# SSRoof.net
KiCad netlist of a schematic drawn in Altium Designer
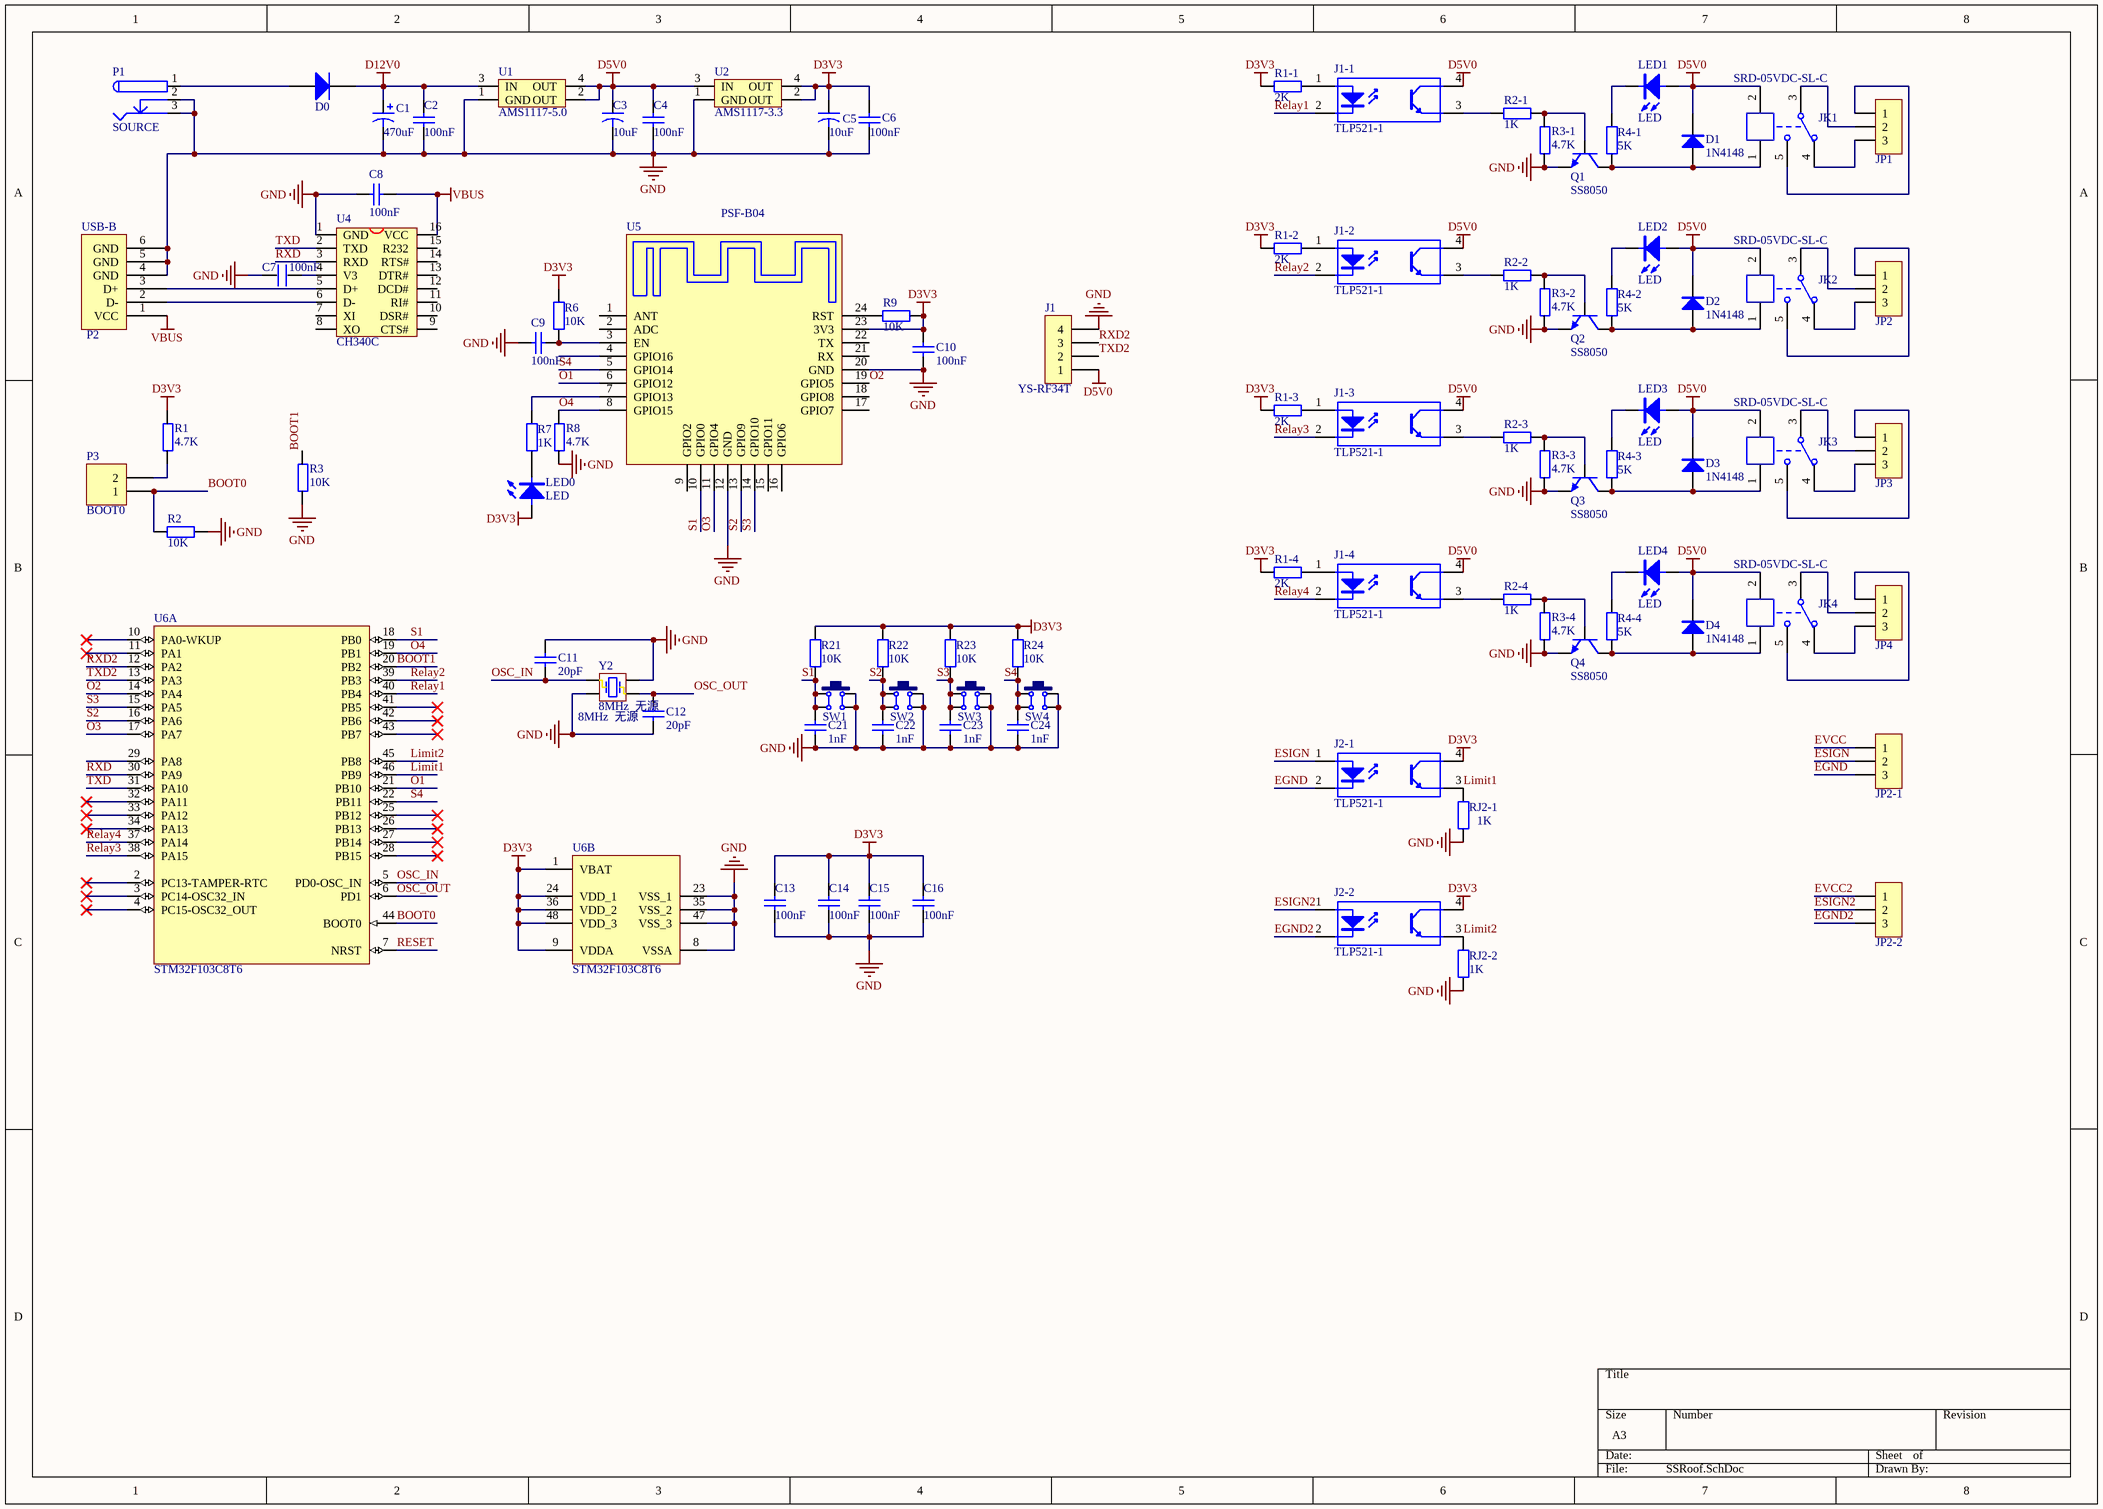
[diagram p0: SSRoof.SchDoc]

(export (version "E")
  (design (tool "Eeschema 10.0.6"))
  (components
    (comp (ref "C1")
      (value "470uF")
      (footprint "CAP8")
      (description "470UF      16V      CD10X10D5")
      (libsource (lib "平台原理图symbol图库V1.0") (part "C470UF016S"))
    )
    (comp (ref "C2")
      (value "100nF")
      (footprint "0603C")
      (description "Capacitor")
      (fields (field (name "PUBLISHER") "Altium Limited"))
      (libsource (lib "Crazy_PCB") (part "Cap"))
    )
    (comp (ref "C3")
      (value "10uF")
      (footprint "3216")
      (fields (field (name "VAULE") "10uF"))
      (libsource (lib "Crazy_PCB") (part "CAP2"))
    )
    (comp (ref "C4")
      (value "100nF")
      (footprint "0603C")
      (description "Capacitor")
      (fields (field (name "PUBLISHER") "Altium Limited"))
      (libsource (lib "Crazy_PCB") (part "Cap"))
    )
    (comp (ref "C5")
      (value "10uF")
      (footprint "3216")
      (fields (field (name "VAULE") "10uF"))
      (libsource (lib "Crazy_PCB") (part "CAP2"))
    )
    (comp (ref "C6")
      (value "100nF")
      (footprint "0603C")
      (description "Capacitor")
      (fields (field (name "PUBLISHER") "Altium Limited"))
      (libsource (lib "Crazy_PCB") (part "Cap"))
    )
    (comp (ref "C7")
      (value "100nF")
      (footprint "0603C")
      (libsource (lib "WarShip V3 STM32103封装库") (part "C"))
    )
    (comp (ref "C8")
      (value "100nF")
      (footprint "0603C")
      (description "Capacitor")
      (fields (field (name "PUBLISHER") "Altium Limited"))
      (libsource (lib "Crazy_PCB") (part "Cap"))
    )
    (comp (ref "C9")
      (value "100nF")
      (footprint "0603C")
      (description "Capacitor")
      (fields (field (name "PUBLISHER") "Altium Limited"))
      (libsource (lib "Crazy_PCB") (part "Cap"))
    )
    (comp (ref "C10")
      (value "100nF")
      (footprint "0603C")
      (description "Capacitor")
      (fields (field (name "PUBLISHER") "Altium Limited"))
      (libsource (lib "Crazy_PCB") (part "Cap"))
    )
    (comp (ref "C11")
      (value "20pF")
      (footprint "0603C")
      (description "Capacitor")
      (fields (field (name "PUBLISHER") "Altium Limited"))
      (libsource (lib "JL_SCH") (part "Cap"))
    )
    (comp (ref "C12")
      (value "20pF")
      (footprint "0603C")
      (description "Capacitor")
      (fields (field (name "PUBLISHER") "Altium Limited"))
      (libsource (lib "JL_SCH") (part "Cap"))
    )
    (comp (ref "C13")
      (value "100nF")
      (footprint "0603C")
      (description "Capacitor")
      (fields (field (name "PUBLISHER") "Altium Limited"))
      (libsource (lib "Crazy_PCB") (part "Cap"))
    )
    (comp (ref "C14")
      (value "100nF")
      (footprint "0603C")
      (description "Capacitor")
      (fields (field (name "PUBLISHER") "Altium Limited"))
      (libsource (lib "Crazy_PCB") (part "Cap"))
    )
    (comp (ref "C15")
      (value "100nF")
      (footprint "0603C")
      (description "Capacitor")
      (fields (field (name "PUBLISHER") "Altium Limited"))
      (libsource (lib "Crazy_PCB") (part "Cap"))
    )
    (comp (ref "C16")
      (value "100nF")
      (footprint "0603C")
      (description "Capacitor")
      (fields (field (name "PUBLISHER") "Altium Limited"))
      (libsource (lib "Crazy_PCB") (part "Cap"))
    )
    (comp (ref "C21")
      (value "1nF")
      (footprint "0603C")
      (description "Capacitor")
      (fields (field (name "PUBLISHER") "Altium Limited"))
      (libsource (lib "JL_SCH") (part "Cap"))
    )
    (comp (ref "C22")
      (value "1nF")
      (footprint "0603C")
      (description "Capacitor")
      (fields (field (name "PUBLISHER") "Altium Limited"))
      (libsource (lib "JL_SCH") (part "Cap"))
    )
    (comp (ref "C23")
      (value "1nF")
      (footprint "0603C")
      (description "Capacitor")
      (fields (field (name "PUBLISHER") "Altium Limited"))
      (libsource (lib "JL_SCH") (part "Cap"))
    )
    (comp (ref "C24")
      (value "1nF")
      (footprint "0603C")
      (description "Capacitor")
      (fields (field (name "PUBLISHER") "Altium Limited"))
      (libsource (lib "JL_SCH") (part "Cap"))
    )
    (comp (ref "D0")
      (value "M7")
      (footprint "DO-214AC")
      (description "High Conductance Fast Diode")
      (fields (field (name "PUBLISHER") "Altium Limited"))
      (libsource (lib "Crazy_PCB") (part "Diode"))
    )
    (comp (ref "D1")
      (value "1N4148")
      (footprint "SOD-323")
      (description "高速开关二极管")
      (fields (field (name "版权归属") "源创客"))
      (libsource (lib "8.1   - 二极管-整流桥") (part "1N4148"))
    )
    (comp (ref "D2")
      (value "1N4148")
      (footprint "SOD-323")
      (description "高速开关二极管")
      (fields (field (name "版权归属") "源创客"))
      (libsource (lib "8.1   - 二极管-整流桥") (part "1N4148"))
    )
    (comp (ref "D3")
      (value "1N4148")
      (footprint "SOD-323")
      (description "高速开关二极管")
      (fields (field (name "版权归属") "源创客"))
      (libsource (lib "8.1   - 二极管-整流桥") (part "1N4148"))
    )
    (comp (ref "D4")
      (value "1N4148")
      (footprint "SOD-323")
      (description "高速开关二极管")
      (fields (field (name "版权归属") "源创客"))
      (libsource (lib "8.1   - 二极管-整流桥") (part "1N4148"))
    )
    (comp (ref "J1")
      (value "YS-RF34T")
      (footprint "PIN-4-2.54-1.0")
      (description "Connector")
      (libsource (lib "General") (part "HDR1x4"))
    )
    (comp (ref "J1-1")
      (value "TLP521-1")
      (footprint "SOP4-W2.54_M")
      (description "1路开关光耦")
      (fields (field (name "版权归属") "源创客"))
      (libsource (lib "11.1 - 传感元件") (part "TLP521-1"))
    )
    (comp (ref "J1-2")
      (value "TLP521-1")
      (footprint "SOP4-W2.54_M")
      (description "1路开关光耦")
      (fields (field (name "版权归属") "源创客"))
      (libsource (lib "11.1 - 传感元件") (part "TLP521-1"))
    )
    (comp (ref "J1-3")
      (value "TLP521-1")
      (footprint "SOP4-W2.54_M")
      (description "1路开关光耦")
      (fields (field (name "版权归属") "源创客"))
      (libsource (lib "11.1 - 传感元件") (part "TLP521-1"))
    )
    (comp (ref "J1-4")
      (value "TLP521-1")
      (footprint "SOP4-W2.54_M")
      (description "1路开关光耦")
      (fields (field (name "版权归属") "源创客"))
      (libsource (lib "11.1 - 传感元件") (part "TLP521-1"))
    )
    (comp (ref "J2-1")
      (value "TLP521-1")
      (footprint "SOP4-W2.54_M")
      (description "1路开关光耦")
      (fields (field (name "版权归属") "源创客"))
      (libsource (lib "11.1 - 传感元件") (part "TLP521-1"))
    )
    (comp (ref "J2-2")
      (value "TLP521-1")
      (footprint "SOP4-W2.54_M")
      (description "1路开关光耦")
      (fields (field (name "版权归属") "源创客"))
      (libsource (lib "11.1 - 传感元件") (part "TLP521-1"))
    )
    (comp (ref "JK1")
      (value "SRD-05VDC-SL-C")
      (footprint "SRD-C_B")
      (description "5V一组转换")
      (fields (field (name "版权归属") "源创客"))
      (libsource (lib "7.1   - 继电器") (part "SRD-05VDC-SL-C"))
    )
    (comp (ref "JK2")
      (value "SRD-05VDC-SL-C")
      (footprint "SRD-C_B")
      (description "5V一组转换")
      (fields (field (name "版权归属") "源创客"))
      (libsource (lib "7.1   - 继电器") (part "SRD-05VDC-SL-C"))
    )
    (comp (ref "JK3")
      (value "SRD-05VDC-SL-C")
      (footprint "SRD-C_B")
      (description "5V一组转换")
      (fields (field (name "版权归属") "源创客"))
      (libsource (lib "7.1   - 继电器") (part "SRD-05VDC-SL-C"))
    )
    (comp (ref "JK4")
      (value "SRD-05VDC-SL-C")
      (footprint "SRD-C_B")
      (description "5V一组转换")
      (fields (field (name "版权归属") "源创客"))
      (libsource (lib "7.1   - 继电器") (part "SRD-05VDC-SL-C"))
    )
    (comp (ref "JP1")
      (value "HDR-1X3")
      (footprint "KF2EDGK5.0-LI-3P")
      (description "3P接插件")
      (fields (field (name "版权归属") "源创客"))
      (libsource (lib "4.9   - 接插件-脚距5.0") (part "Header 3"))
    )
    (comp (ref "JP2")
      (value "HDR-1X3")
      (footprint "KF2EDGK5.0-LI-3P")
      (description "3P接插件")
      (fields (field (name "版权归属") "源创客"))
      (libsource (lib "4.9   - 接插件-脚距5.0") (part "Header 3"))
    )
    (comp (ref "JP2-1")
      (value "HDR-1X3")
      (footprint "KF2EDGK5.0-LI-3P")
      (description "3P接插件")
      (fields (field (name "版权归属") "源创客"))
      (libsource (lib "4.9   - 接插件-脚距5.0") (part "Header 3"))
    )
    (comp (ref "JP2-2")
      (value "HDR-1X3")
      (footprint "KF2EDGK5.0-LI-3P")
      (description "3P接插件")
      (fields (field (name "版权归属") "源创客"))
      (libsource (lib "4.9   - 接插件-脚距5.0") (part "Header 3"))
    )
    (comp (ref "JP3")
      (value "HDR-1X3")
      (footprint "KF2EDGK5.0-LI-3P")
      (description "3P接插件")
      (fields (field (name "版权归属") "源创客"))
      (libsource (lib "4.9   - 接插件-脚距5.0") (part "Header 3"))
    )
    (comp (ref "JP4")
      (value "HDR-1X3")
      (footprint "KF2EDGK5.0-LI-3P")
      (description "3P接插件")
      (fields (field (name "版权归属") "源创客"))
      (libsource (lib "4.9   - 接插件-脚距5.0") (part "Header 3"))
    )
    (comp (ref "LED0") (value "LED") (footprint "LED-0603") (libsource (lib "General") (part "LED")))
    (comp (ref "LED1") (value "LED") (footprint "LED-0603") (libsource (lib "General") (part "LED")))
    (comp (ref "LED2") (value "LED") (footprint "LED-0603") (libsource (lib "General") (part "LED")))
    (comp (ref "LED3") (value "LED") (footprint "LED-0603") (libsource (lib "General") (part "LED")))
    (comp (ref "LED4") (value "LED") (footprint "LED-0603") (libsource (lib "General") (part "LED")))
    (comp (ref "P1")
      (value "SOURCE")
      (footprint "DC_5.5MM")
      (fields (field (name "PUBLISHER") "Altium Limited"))
      (libsource (lib "Crazy_PCB") (part "SOURCE"))
    )
    (comp (ref "P2") (value "USB-B") (footprint "USB-B") (libsource (lib "DX") (part "USB-B")))
    (comp (ref "P3")
      (value "BOOT0")
      (footprint "HDR1X2")
      (description "Header, 2-Pin")
      (fields (field (name "PUBLISHER") "Altium Limited"))
      (libsource (lib "Miscellaneous Connectors") (part "MHDR1X2"))
    )
    (comp (ref "Q1")
      (value "SS8050")
      (footprint "SOT23-3N")
      (description "高频放大-NPN型")
      (fields (field (name "版权归属") "源创客"))
      (libsource (lib "6.2   - 三极管") (part "8050-SMD"))
    )
    (comp (ref "Q2")
      (value "SS8050")
      (footprint "SOT23-3N")
      (description "高频放大-NPN型")
      (fields (field (name "版权归属") "源创客"))
      (libsource (lib "6.2   - 三极管") (part "8050-SMD"))
    )
    (comp (ref "Q3")
      (value "SS8050")
      (footprint "SOT23-3N")
      (description "高频放大-NPN型")
      (fields (field (name "版权归属") "源创客"))
      (libsource (lib "6.2   - 三极管") (part "8050-SMD"))
    )
    (comp (ref "Q4")
      (value "SS8050")
      (footprint "SOT23-3N")
      (description "高频放大-NPN型")
      (fields (field (name "版权归属") "源创客"))
      (libsource (lib "6.2   - 三极管") (part "8050-SMD"))
    )
    (comp (ref "R1") (value "4.7K") (footprint "0603R") (libsource (lib "WarShip V3 STM32103封装库") (part "R")))
    (comp (ref "R1-1")
      (value "2K")
      (footprint "0603R")
      (description "Resistor")
      (fields (field (name "PUBLISHER") "Altium Limited"))
      (libsource (lib "") (part "RES_1"))
    )
    (comp (ref "R1-2")
      (value "2K")
      (footprint "0603R")
      (description "Resistor")
      (fields (field (name "PUBLISHER") "Altium Limited"))
      (libsource (lib "") (part "RES_1"))
    )
    (comp (ref "R1-3")
      (value "2K")
      (footprint "0603R")
      (description "Resistor")
      (fields (field (name "PUBLISHER") "Altium Limited"))
      (libsource (lib "") (part "RES_1"))
    )
    (comp (ref "R1-4")
      (value "2K")
      (footprint "0603R")
      (description "Resistor")
      (fields (field (name "PUBLISHER") "Altium Limited"))
      (libsource (lib "") (part "RES_1"))
    )
    (comp (ref "R2")
      (value "10K")
      (footprint "0603R")
      (description "Resistor")
      (fields (field (name "PUBLISHER") "Altium Limited"))
      (libsource (lib "Crazy_PCB") (part "RES"))
    )
    (comp (ref "R2-1")
      (value "1K")
      (footprint "0603R")
      (description "Resistor")
      (fields (field (name "PUBLISHER") "Altium Limited"))
      (libsource (lib "") (part "RES_1"))
    )
    (comp (ref "R2-2")
      (value "1K")
      (footprint "0603R")
      (description "Resistor")
      (fields (field (name "PUBLISHER") "Altium Limited"))
      (libsource (lib "") (part "RES_1"))
    )
    (comp (ref "R2-3")
      (value "1K")
      (footprint "0603R")
      (description "Resistor")
      (fields (field (name "PUBLISHER") "Altium Limited"))
      (libsource (lib "") (part "RES_1"))
    )
    (comp (ref "R2-4")
      (value "1K")
      (footprint "0603R")
      (description "Resistor")
      (fields (field (name "PUBLISHER") "Altium Limited"))
      (libsource (lib "") (part "RES_1"))
    )
    (comp (ref "R3") (value "10K") (footprint "0603R") (libsource (lib "WarShip V3 STM32103封装库") (part "R")))
    (comp (ref "R3-1")
      (value "4.7K")
      (footprint "0603R")
      (libsource (lib "WarShip V3 STM32103封装库") (part "R"))
    )
    (comp (ref "R3-2")
      (value "4.7K")
      (footprint "0603R")
      (libsource (lib "WarShip V3 STM32103封装库") (part "R"))
    )
    (comp (ref "R3-3")
      (value "4.7K")
      (footprint "0603R")
      (libsource (lib "WarShip V3 STM32103封装库") (part "R"))
    )
    (comp (ref "R3-4")
      (value "4.7K")
      (footprint "0603R")
      (libsource (lib "WarShip V3 STM32103封装库") (part "R"))
    )
    (comp (ref "R4-1")
      (value "5K")
      (footprint "0603R")
      (description "Resistor")
      (fields (field (name "PUBLISHER") "Altium Limited"))
      (libsource (lib "") (part "RES_3"))
    )
    (comp (ref "R4-2")
      (value "5K")
      (footprint "0603R")
      (description "Resistor")
      (fields (field (name "PUBLISHER") "Altium Limited"))
      (libsource (lib "") (part "RES_3"))
    )
    (comp (ref "R4-3")
      (value "5K")
      (footprint "0603R")
      (description "Resistor")
      (fields (field (name "PUBLISHER") "Altium Limited"))
      (libsource (lib "") (part "RES_3"))
    )
    (comp (ref "R4-4")
      (value "5K")
      (footprint "0603R")
      (description "Resistor")
      (fields (field (name "PUBLISHER") "Altium Limited"))
      (libsource (lib "") (part "RES_3"))
    )
    (comp (ref "R6")
      (value "10K")
      (footprint "0603R")
      (description "Resistor")
      (fields (field (name "PUBLISHER") "Altium Limited"))
      (libsource (lib "") (part "RES_2"))
    )
    (comp (ref "R7")
      (value "1K")
      (footprint "0603R")
      (description "Resistor")
      (fields (field (name "PUBLISHER") "Altium Limited"))
      (libsource (lib "") (part "RES_3"))
    )
    (comp (ref "R8") (value "4.7K") (footprint "0603R") (libsource (lib "WarShip V3 STM32103封装库") (part "R")))
    (comp (ref "R9")
      (value "10K")
      (footprint "0603R")
      (description "Resistor")
      (fields (field (name "PUBLISHER") "Altium Limited"))
      (libsource (lib "Crazy_PCB") (part "RES"))
    )
    (comp (ref "R21")
      (value "10K")
      (footprint "0603R")
      (description "Resistor")
      (fields (field (name "PUBLISHER") "Altium Limited"))
      (libsource (lib "") (part "RES_2"))
    )
    (comp (ref "R22")
      (value "10K")
      (footprint "0603R")
      (description "Resistor")
      (fields (field (name "PUBLISHER") "Altium Limited"))
      (libsource (lib "") (part "RES_2"))
    )
    (comp (ref "R23")
      (value "10K")
      (footprint "0603R")
      (description "Resistor")
      (fields (field (name "PUBLISHER") "Altium Limited"))
      (libsource (lib "") (part "RES_2"))
    )
    (comp (ref "R24")
      (value "10K")
      (footprint "0603R")
      (description "Resistor")
      (fields (field (name "PUBLISHER") "Altium Limited"))
      (libsource (lib "") (part "RES_2"))
    )
    (comp (ref "RJ2-1")
      (value "1K")
      (footprint "0603R")
      (description "Resistor")
      (fields (field (name "PUBLISHER") "Altium Limited"))
      (libsource (lib "") (part "RES_2"))
    )
    (comp (ref "RJ2-2")
      (value "1K")
      (footprint "0603R")
      (description "Resistor")
      (fields (field (name "PUBLISHER") "Altium Limited"))
      (libsource (lib "") (part "RES_2"))
    )
    (comp (ref "SW1")
      (value "6x6x5")
      (footprint "TSW SMD-6*6*6")
      (description "贴片6x6轻触开关")
      (fields (field (name "版权归属") "源创客"))
      (libsource (lib "5.1   - 按键-开关") (part "TSW SMD-6x6"))
    )
    (comp (ref "SW2")
      (value "6x6x5")
      (footprint "TSW SMD-6*6*6")
      (description "贴片6x6轻触开关")
      (fields (field (name "版权归属") "源创客"))
      (libsource (lib "5.1   - 按键-开关") (part "TSW SMD-6x6"))
    )
    (comp (ref "SW3")
      (value "6x6x5")
      (footprint "TSW SMD-6*6*6")
      (description "贴片6x6轻触开关")
      (fields (field (name "版权归属") "源创客"))
      (libsource (lib "5.1   - 按键-开关") (part "TSW SMD-6x6"))
    )
    (comp (ref "SW4")
      (value "6x6x5")
      (footprint "TSW SMD-6*6*6")
      (description "贴片6x6轻触开关")
      (fields (field (name "版权归属") "源创客"))
      (libsource (lib "5.1   - 按键-开关") (part "TSW SMD-6x6"))
    )
    (comp (ref "U1")
      (value "AMS1117-5.0")
      (footprint "SOT223")
      (libsource (lib "MiniSTM32 V3.0封装库") (part "AMS1117"))
    )
    (comp (ref "U2")
      (value "AMS1117-3.3")
      (footprint "SOT223")
      (libsource (lib "MiniSTM32 V3.0封装库") (part "AMS1117"))
    )
    (comp (ref "U4")
      (value "CH340C")
      (footprint "SO-16")
      (description "USB2UART")
      (libsource (lib "WarShip V3 STM32103封装库") (part "CH340G"))
    )
    (comp (ref "U5") (value "PSF-B04") (footprint "PSF-B04") (libsource (lib "SS") (part "PSF-B04")))
    (comp (ref "U6")
      (value "STM32F103C8T6")
      (footprint "LQFP48_N")
      (libsource (lib "STMicroelectronics STM32 F1") (part "STM32F103C8T6"))
    )
    (comp (ref "Y2")
      (value "8MHz  无源")
      (footprint "X3225")
      (description "Crystal Oscillator")
      (fields (field (name "ALTIUM_VALUE") "8MHz  无源") (field (name "PUBLISHER") "Altium Limited"))
      (libsource (lib "JL_SCH") (part "XTAL_1"))
    )
  )
  (nets
    (net (code "1") (name "/BOOT0") (class "Default")
      (node (ref "P3") (pin "1") (pinfunction "1_1") (pintype "passive"))
      (node (ref "R2") (pin "1") (pinfunction "1_1") (pintype "passive"))
      (node (ref "U6") (pin "44") (pinfunction "BOOT0_44") (pintype "input"))
    )
    (net (code "2") (name "/BOOT1") (class "Default")
      (node (ref "R3") (pin "2") (pintype "passive"))
      (node (ref "U6") (pin "20") (pinfunction "PB2_20") (pintype "bidirectional"))
    )
    (net (code "3") (name "/EGND") (class "Default")
      (node (ref "J2-1") (pin "2") (pinfunction "K_2") (pintype "passive"))
      (node (ref "JP2-1") (pin "3") (pinfunction "3_3") (pintype "passive"))
    )
    (net (code "4") (name "/EGND2") (class "Default")
      (node (ref "J2-2") (pin "2") (pinfunction "K_2") (pintype "passive"))
      (node (ref "JP2-2") (pin "3") (pinfunction "3_3") (pintype "passive"))
    )
    (net (code "5") (name "/ESIGN") (class "Default")
      (node (ref "J2-1") (pin "1") (pinfunction "A_1") (pintype "passive"))
      (node (ref "JP2-1") (pin "2") (pinfunction "2_2") (pintype "passive"))
    )
    (net (code "6") (name "/ESIGN2") (class "Default")
      (node (ref "J2-2") (pin "1") (pinfunction "A_1") (pintype "passive"))
      (node (ref "JP2-2") (pin "2") (pinfunction "2_2") (pintype "passive"))
    )
    (net (code "7") (name "/EVCC") (class "Default")
      (node (ref "JP2-1") (pin "1") (pinfunction "1_1") (pintype "passive"))
    )
    (net (code "8") (name "/EVCC2") (class "Default")
      (node (ref "JP2-2") (pin "1") (pinfunction "1_1") (pintype "passive"))
    )
    (net (code "9") (name "/Limit1") (class "Default")
      (node (ref "J2-1") (pin "3") (pinfunction "E_3") (pintype "passive"))
      (node (ref "RJ2-1") (pin "2") (pinfunction "2_2") (pintype "passive"))
      (node (ref "U6") (pin "46") (pinfunction "PB9_46") (pintype "bidirectional"))
    )
    (net (code "10") (name "/Limit2") (class "Default")
      (node (ref "J2-2") (pin "3") (pinfunction "E_3") (pintype "passive"))
      (node (ref "RJ2-2") (pin "2") (pinfunction "2_2") (pintype "passive"))
      (node (ref "U6") (pin "45") (pinfunction "PB8_45") (pintype "bidirectional"))
    )
    (net (code "11") (name "/O1") (class "Default")
      (node (ref "U5") (pin "6") (pinfunction "GPIO12_6") (pintype "passive"))
      (node (ref "U6") (pin "21") (pinfunction "PB10_21") (pintype "bidirectional"))
    )
    (net (code "12") (name "/O2") (class "Default")
      (node (ref "U5") (pin "19") (pinfunction "GPIO5_19") (pintype "passive"))
      (node (ref "U6") (pin "14") (pinfunction "PA4_14") (pintype "bidirectional"))
    )
    (net (code "13") (name "/O3") (class "Default")
      (node (ref "U5") (pin "11") (pinfunction "GPIO4_11") (pintype "passive"))
      (node (ref "U6") (pin "17") (pinfunction "PA7_17") (pintype "bidirectional"))
    )
    (net (code "14") (name "/O4") (class "Default")
      (node (ref "R8") (pin "2") (pintype "passive"))
      (node (ref "U5") (pin "8") (pinfunction "GPIO15_8") (pintype "passive"))
      (node (ref "U6") (pin "19") (pinfunction "PB1_19") (pintype "bidirectional"))
    )
    (net (code "15") (name "/OSC_IN") (class "Default")
      (node (ref "C11") (pin "1") (pinfunction "1_1") (pintype "passive"))
      (node (ref "U6") (pin "5") (pinfunction "PD0-OSC_IN_5") (pintype "bidirectional"))
      (node (ref "Y2") (pin "1") (pinfunction "OSC1_1") (pintype "passive"))
    )
    (net (code "16") (name "/OSC_OUT") (class "Default")
      (node (ref "C12") (pin "1") (pinfunction "1_1") (pintype "passive"))
      (node (ref "U6") (pin "6") (pinfunction "PD1_6") (pintype "bidirectional"))
      (node (ref "Y2") (pin "3") (pinfunction "OSC2_3") (pintype "passive"))
    )
    (net (code "17") (name "/RESET") (class "Default")
      (node (ref "U6") (pin "7") (pinfunction "NRST_7") (pintype "bidirectional"))
    )
    (net (code "18") (name "/RXD") (class "Default")
      (node (ref "U4") (pin "3") (pinfunction "RXD_3") (pintype "passive"))
      (node (ref "U6") (pin "30") (pinfunction "PA9_30") (pintype "bidirectional"))
    )
    (net (code "19") (name "/RXD2") (class "Default")
      (node (ref "J1") (pin "3") (pinfunction "3_3") (pintype "passive"))
      (node (ref "U6") (pin "12") (pinfunction "PA2_12") (pintype "bidirectional"))
    )
    (net (code "20") (name "/Relay1") (class "Default")
      (node (ref "J1-1") (pin "2") (pinfunction "K_2") (pintype "passive"))
      (node (ref "U6") (pin "40") (pinfunction "PB4_40") (pintype "bidirectional"))
    )
    (net (code "21") (name "/Relay2") (class "Default")
      (node (ref "J1-2") (pin "2") (pinfunction "K_2") (pintype "passive"))
      (node (ref "U6") (pin "39") (pinfunction "PB3_39") (pintype "bidirectional"))
    )
    (net (code "22") (name "/Relay3") (class "Default")
      (node (ref "J1-3") (pin "2") (pinfunction "K_2") (pintype "passive"))
      (node (ref "U6") (pin "38") (pinfunction "PA15_38") (pintype "bidirectional"))
    )
    (net (code "23") (name "/Relay4") (class "Default")
      (node (ref "J1-4") (pin "2") (pinfunction "K_2") (pintype "passive"))
      (node (ref "U6") (pin "37") (pinfunction "PA14_37") (pintype "bidirectional"))
    )
    (net (code "24") (name "/S1") (class "Default")
      (node (ref "C21") (pin "1") (pinfunction "1_1") (pintype "passive"))
      (node (ref "R21") (pin "1") (pinfunction "1_1") (pintype "passive"))
      (node (ref "SW1") (pin "1") (pinfunction "1_1") (pintype "passive"))
      (node (ref "SW1") (pin "4") (pinfunction "4_4") (pintype "passive"))
      (node (ref "U5") (pin "10") (pinfunction "GPIO0_10") (pintype "passive"))
      (node (ref "U6") (pin "18") (pinfunction "PB0_18") (pintype "bidirectional"))
    )
    (net (code "25") (name "/S2") (class "Default")
      (node (ref "C22") (pin "1") (pinfunction "1_1") (pintype "passive"))
      (node (ref "R22") (pin "1") (pinfunction "1_1") (pintype "passive"))
      (node (ref "SW2") (pin "1") (pinfunction "1_1") (pintype "passive"))
      (node (ref "SW2") (pin "4") (pinfunction "4_4") (pintype "passive"))
      (node (ref "U5") (pin "13") (pinfunction "GPIO9_13") (pintype "passive"))
      (node (ref "U6") (pin "16") (pinfunction "PA6_16") (pintype "bidirectional"))
    )
    (net (code "26") (name "/S3") (class "Default")
      (node (ref "C23") (pin "1") (pinfunction "1_1") (pintype "passive"))
      (node (ref "R23") (pin "1") (pinfunction "1_1") (pintype "passive"))
      (node (ref "SW3") (pin "1") (pinfunction "1_1") (pintype "passive"))
      (node (ref "SW3") (pin "4") (pinfunction "4_4") (pintype "passive"))
      (node (ref "U5") (pin "14") (pinfunction "GPIO10_14") (pintype "passive"))
      (node (ref "U6") (pin "15") (pinfunction "PA5_15") (pintype "bidirectional"))
    )
    (net (code "27") (name "/S4") (class "Default")
      (node (ref "C24") (pin "1") (pinfunction "1_1") (pintype "passive"))
      (node (ref "R24") (pin "1") (pinfunction "1_1") (pintype "passive"))
      (node (ref "SW4") (pin "1") (pinfunction "1_1") (pintype "passive"))
      (node (ref "SW4") (pin "4") (pinfunction "4_4") (pintype "passive"))
      (node (ref "U5") (pin "5") (pinfunction "GPIO14_5") (pintype "passive"))
      (node (ref "U6") (pin "22") (pinfunction "PB11_22") (pintype "bidirectional"))
    )
    (net (code "28") (name "/TXD") (class "Default")
      (node (ref "U4") (pin "2") (pinfunction "TXD_2") (pintype "passive"))
      (node (ref "U6") (pin "31") (pinfunction "PA10_31") (pintype "bidirectional"))
    )
    (net (code "29") (name "/TXD2") (class "Default")
      (node (ref "J1") (pin "2") (pinfunction "2_2") (pintype "passive"))
      (node (ref "U6") (pin "13") (pinfunction "PA3_13") (pintype "bidirectional"))
    )
    (net (code "30") (name "D3V3") (class "Default")
      (node (ref "C10") (pin "1") (pinfunction "1_1") (pintype "passive"))
      (node (ref "C13") (pin "2") (pinfunction "2_2") (pintype "passive"))
      (node (ref "C14") (pin "2") (pinfunction "2_2") (pintype "passive"))
      (node (ref "C15") (pin "2") (pinfunction "2_2") (pintype "passive"))
      (node (ref "C16") (pin "2") (pinfunction "2_2") (pintype "passive"))
      (node (ref "C5") (pin "1") (pinfunction "1_1") (pintype "passive"))
      (node (ref "C6") (pin "2") (pinfunction "2_2") (pintype "passive"))
      (node (ref "J2-1") (pin "4") (pinfunction "C_4") (pintype "passive"))
      (node (ref "J2-2") (pin "4") (pinfunction "C_4") (pintype "passive"))
      (node (ref "LED0") (pin "1") (pinfunction "A_1") (pintype "passive"))
      (node (ref "R1") (pin "2") (pintype "passive"))
      (node (ref "R1-1") (pin "2") (pinfunction "2_2") (pintype "passive"))
      (node (ref "R1-2") (pin "2") (pinfunction "2_2") (pintype "passive"))
      (node (ref "R1-3") (pin "2") (pinfunction "2_2") (pintype "passive"))
      (node (ref "R1-4") (pin "2") (pinfunction "2_2") (pintype "passive"))
      (node (ref "R21") (pin "2") (pinfunction "2_2") (pintype "passive"))
      (node (ref "R22") (pin "2") (pinfunction "2_2") (pintype "passive"))
      (node (ref "R23") (pin "2") (pinfunction "2_2") (pintype "passive"))
      (node (ref "R24") (pin "2") (pinfunction "2_2") (pintype "passive"))
      (node (ref "R6") (pin "2") (pinfunction "2_2") (pintype "passive"))
      (node (ref "R9") (pin "2") (pinfunction "2_2") (pintype "passive"))
      (node (ref "U2") (pin "2") (pinfunction "OUT_2") (pintype "passive"))
      (node (ref "U2") (pin "4") (pinfunction "OUT_4") (pintype "passive"))
      (node (ref "U5") (pin "23") (pinfunction "3V3_23") (pintype "passive"))
      (node (ref "U6") (pin "1") (pinfunction "VBAT_1") (pintype "power_in"))
      (node (ref "U6") (pin "24") (pinfunction "VDD_1_24") (pintype "power_in"))
      (node (ref "U6") (pin "36") (pinfunction "VDD_2_36") (pintype "power_in"))
      (node (ref "U6") (pin "48") (pinfunction "VDD_3_48") (pintype "power_in"))
      (node (ref "U6") (pin "9") (pinfunction "VDDA_9") (pintype "power_in"))
    )
    (net (code "31") (name "D5V0") (class "Default")
      (node (ref "C3") (pin "1") (pinfunction "1_1") (pintype "passive"))
      (node (ref "C4") (pin "2") (pinfunction "2_2") (pintype "passive"))
      (node (ref "D1") (pin "2") (pinfunction "K_2") (pintype "passive"))
      (node (ref "D2") (pin "2") (pinfunction "K_2") (pintype "passive"))
      (node (ref "D3") (pin "2") (pinfunction "K_2") (pintype "passive"))
      (node (ref "D4") (pin "2") (pinfunction "K_2") (pintype "passive"))
      (node (ref "J1") (pin "1") (pinfunction "1_1") (pintype "passive"))
      (node (ref "J1-1") (pin "4") (pinfunction "C_4") (pintype "passive"))
      (node (ref "J1-2") (pin "4") (pinfunction "C_4") (pintype "passive"))
      (node (ref "J1-3") (pin "4") (pinfunction "C_4") (pintype "passive"))
      (node (ref "J1-4") (pin "4") (pinfunction "C_4") (pintype "passive"))
      (node (ref "JK1") (pin "2") (pinfunction "2_2") (pintype "passive"))
      (node (ref "JK2") (pin "2") (pinfunction "2_2") (pintype "passive"))
      (node (ref "JK3") (pin "2") (pinfunction "2_2") (pintype "passive"))
      (node (ref "JK4") (pin "2") (pinfunction "2_2") (pintype "passive"))
      (node (ref "LED1") (pin "1") (pinfunction "A_1") (pintype "passive"))
      (node (ref "LED2") (pin "1") (pinfunction "A_1") (pintype "passive"))
      (node (ref "LED3") (pin "1") (pinfunction "A_1") (pintype "passive"))
      (node (ref "LED4") (pin "1") (pinfunction "A_1") (pintype "passive"))
      (node (ref "U1") (pin "2") (pinfunction "OUT_2") (pintype "passive"))
      (node (ref "U1") (pin "4") (pinfunction "OUT_4") (pintype "passive"))
      (node (ref "U2") (pin "3") (pinfunction "IN_3") (pintype "passive"))
    )
    (net (code "32") (name "D12V0") (class "Default")
      (node (ref "C1") (pin "1") (pinfunction "1_1") (pintype "passive"))
      (node (ref "C2") (pin "2") (pinfunction "2_2") (pintype "passive"))
      (node (ref "D0") (pin "2") (pinfunction "K_2") (pintype "passive"))
      (node (ref "U1") (pin "3") (pinfunction "IN_3") (pintype "passive"))
    )
    (net (code "33") (name "GND") (class "Default")
      (node (ref "C1") (pin "2") (pinfunction "2_2") (pintype "passive"))
      (node (ref "C10") (pin "2") (pinfunction "2_2") (pintype "passive"))
      (node (ref "C11") (pin "2") (pinfunction "2_2") (pintype "passive"))
      (node (ref "C12") (pin "2") (pinfunction "2_2") (pintype "passive"))
      (node (ref "C13") (pin "1") (pinfunction "1_1") (pintype "passive"))
      (node (ref "C14") (pin "1") (pinfunction "1_1") (pintype "passive"))
      (node (ref "C15") (pin "1") (pinfunction "1_1") (pintype "passive"))
      (node (ref "C16") (pin "1") (pinfunction "1_1") (pintype "passive"))
      (node (ref "C2") (pin "1") (pinfunction "1_1") (pintype "passive"))
      (node (ref "C21") (pin "2") (pinfunction "2_2") (pintype "passive"))
      (node (ref "C22") (pin "2") (pinfunction "2_2") (pintype "passive"))
      (node (ref "C23") (pin "2") (pinfunction "2_2") (pintype "passive"))
      (node (ref "C24") (pin "2") (pinfunction "2_2") (pintype "passive"))
      (node (ref "C3") (pin "2") (pinfunction "2_2") (pintype "passive"))
      (node (ref "C4") (pin "1") (pinfunction "1_1") (pintype "passive"))
      (node (ref "C5") (pin "2") (pinfunction "2_2") (pintype "passive"))
      (node (ref "C6") (pin "1") (pinfunction "1_1") (pintype "passive"))
      (node (ref "C7") (pin "1") (pintype "passive"))
      (node (ref "C8") (pin "1") (pinfunction "1_1") (pintype "passive"))
      (node (ref "C9") (pin "2") (pinfunction "2_2") (pintype "passive"))
      (node (ref "J1") (pin "4") (pinfunction "4_4") (pintype "passive"))
      (node (ref "P1") (pin "2") (pinfunction "2_2") (pintype "power_in"))
      (node (ref "P1") (pin "3") (pinfunction "3_3") (pintype "power_in"))
      (node (ref "P2") (pin "4") (pinfunction "GND_4") (pintype "passive"))
      (node (ref "P2") (pin "5") (pinfunction "GND_5") (pintype "passive"))
      (node (ref "P2") (pin "6") (pinfunction "GND_6") (pintype "passive"))
      (node (ref "Q1") (pin "2") (pinfunction "E_2") (pintype "passive"))
      (node (ref "Q2") (pin "2") (pinfunction "E_2") (pintype "passive"))
      (node (ref "Q3") (pin "2") (pinfunction "E_2") (pintype "passive"))
      (node (ref "Q4") (pin "2") (pinfunction "E_2") (pintype "passive"))
      (node (ref "R2") (pin "2") (pinfunction "2_2") (pintype "passive"))
      (node (ref "R3") (pin "1") (pintype "passive"))
      (node (ref "R3-1") (pin "1") (pintype "passive"))
      (node (ref "R3-2") (pin "1") (pintype "passive"))
      (node (ref "R3-3") (pin "1") (pintype "passive"))
      (node (ref "R3-4") (pin "1") (pintype "passive"))
      (node (ref "R8") (pin "1") (pintype "passive"))
      (node (ref "RJ2-1") (pin "1") (pinfunction "1_1") (pintype "passive"))
      (node (ref "RJ2-2") (pin "1") (pinfunction "1_1") (pintype "passive"))
      (node (ref "SW1") (pin "2") (pinfunction "2_2") (pintype "passive"))
      (node (ref "SW1") (pin "3") (pinfunction "3_3") (pintype "passive"))
      (node (ref "SW2") (pin "2") (pinfunction "2_2") (pintype "passive"))
      (node (ref "SW2") (pin "3") (pinfunction "3_3") (pintype "passive"))
      (node (ref "SW3") (pin "2") (pinfunction "2_2") (pintype "passive"))
      (node (ref "SW3") (pin "3") (pinfunction "3_3") (pintype "passive"))
      (node (ref "SW4") (pin "2") (pinfunction "2_2") (pintype "passive"))
      (node (ref "SW4") (pin "3") (pinfunction "3_3") (pintype "passive"))
      (node (ref "U1") (pin "1") (pinfunction "GND_1") (pintype "passive"))
      (node (ref "U2") (pin "1") (pinfunction "GND_1") (pintype "passive"))
      (node (ref "U4") (pin "1") (pinfunction "GND_1") (pintype "passive"))
      (node (ref "U5") (pin "12") (pinfunction "GND_12") (pintype "passive"))
      (node (ref "U5") (pin "20") (pinfunction "GND_20") (pintype "passive"))
      (node (ref "U6") (pin "23") (pinfunction "VSS_1_23") (pintype "power_in"))
      (node (ref "U6") (pin "35") (pinfunction "VSS_2_35") (pintype "power_in"))
      (node (ref "U6") (pin "47") (pinfunction "VSS_3_47") (pintype "power_in"))
      (node (ref "U6") (pin "8") (pinfunction "VSSA_8") (pintype "power_in"))
      (node (ref "Y2") (pin "2") (pinfunction "NA_2") (pintype "passive"))
      (node (ref "Y2") (pin "4") (pinfunction "NA_4") (pintype "passive"))
    )
    (net (code "34") (name "Net-(D0-A)") (class "Default")
      (node (ref "D0") (pin "1") (pinfunction "A_1") (pintype "passive"))
      (node (ref "P1") (pin "1") (pinfunction "1_1") (pintype "power_in"))
    )
    (net (code "35") (name "Net-(D1-A)") (class "Default")
      (node (ref "D1") (pin "1") (pinfunction "A_1") (pintype "passive"))
      (node (ref "JK1") (pin "1") (pinfunction "1_1") (pintype "passive"))
      (node (ref "Q1") (pin "3") (pinfunction "C_3") (pintype "passive"))
      (node (ref "R4-1") (pin "2") (pinfunction "2_2") (pintype "passive"))
    )
    (net (code "36") (name "Net-(D2-A)") (class "Default")
      (node (ref "D2") (pin "1") (pinfunction "A_1") (pintype "passive"))
      (node (ref "JK2") (pin "1") (pinfunction "1_1") (pintype "passive"))
      (node (ref "Q2") (pin "3") (pinfunction "C_3") (pintype "passive"))
      (node (ref "R4-2") (pin "2") (pinfunction "2_2") (pintype "passive"))
    )
    (net (code "37") (name "Net-(D3-A)") (class "Default")
      (node (ref "D3") (pin "1") (pinfunction "A_1") (pintype "passive"))
      (node (ref "JK3") (pin "1") (pinfunction "1_1") (pintype "passive"))
      (node (ref "Q3") (pin "3") (pinfunction "C_3") (pintype "passive"))
      (node (ref "R4-3") (pin "2") (pinfunction "2_2") (pintype "passive"))
    )
    (net (code "38") (name "Net-(D4-A)") (class "Default")
      (node (ref "D4") (pin "1") (pinfunction "A_1") (pintype "passive"))
      (node (ref "JK4") (pin "1") (pinfunction "1_1") (pintype "passive"))
      (node (ref "Q4") (pin "3") (pinfunction "C_3") (pintype "passive"))
      (node (ref "R4-4") (pin "2") (pinfunction "2_2") (pintype "passive"))
    )
    (net (code "39") (name "Net-(J1-1-A)") (class "Default")
      (node (ref "J1-1") (pin "1") (pinfunction "A_1") (pintype "passive"))
      (node (ref "R1-1") (pin "1") (pinfunction "1_1") (pintype "passive"))
    )
    (net (code "40") (name "Net-(J1-1-E)") (class "Default")
      (node (ref "J1-1") (pin "3") (pinfunction "E_3") (pintype "passive"))
      (node (ref "R2-1") (pin "2") (pinfunction "2_2") (pintype "passive"))
    )
    (net (code "41") (name "Net-(J1-2-A)") (class "Default")
      (node (ref "J1-2") (pin "1") (pinfunction "A_1") (pintype "passive"))
      (node (ref "R1-2") (pin "1") (pinfunction "1_1") (pintype "passive"))
    )
    (net (code "42") (name "Net-(J1-2-E)") (class "Default")
      (node (ref "J1-2") (pin "3") (pinfunction "E_3") (pintype "passive"))
      (node (ref "R2-2") (pin "2") (pinfunction "2_2") (pintype "passive"))
    )
    (net (code "43") (name "Net-(J1-3-A)") (class "Default")
      (node (ref "J1-3") (pin "1") (pinfunction "A_1") (pintype "passive"))
      (node (ref "R1-3") (pin "1") (pinfunction "1_1") (pintype "passive"))
    )
    (net (code "44") (name "Net-(J1-3-E)") (class "Default")
      (node (ref "J1-3") (pin "3") (pinfunction "E_3") (pintype "passive"))
      (node (ref "R2-3") (pin "2") (pinfunction "2_2") (pintype "passive"))
    )
    (net (code "45") (name "Net-(J1-4-A)") (class "Default")
      (node (ref "J1-4") (pin "1") (pinfunction "A_1") (pintype "passive"))
      (node (ref "R1-4") (pin "1") (pinfunction "1_1") (pintype "passive"))
    )
    (net (code "46") (name "Net-(J1-4-E)") (class "Default")
      (node (ref "J1-4") (pin "3") (pinfunction "E_3") (pintype "passive"))
      (node (ref "R2-4") (pin "2") (pinfunction "2_2") (pintype "passive"))
    )
    (net (code "47") (name "Net-(JK1-Pad3)") (class "Default")
      (node (ref "JK1") (pin "3") (pinfunction "3_3") (pintype "passive"))
      (node (ref "JP1") (pin "2") (pinfunction "2_2") (pintype "passive"))
    )
    (net (code "48") (name "Net-(JK1-Pad4)") (class "Default")
      (node (ref "JK1") (pin "4") (pinfunction "4_4") (pintype "passive"))
      (node (ref "JP1") (pin "3") (pinfunction "3_3") (pintype "passive"))
    )
    (net (code "49") (name "Net-(JK1-Pad5)") (class "Default")
      (node (ref "JK1") (pin "5") (pinfunction "5_5") (pintype "passive"))
      (node (ref "JP1") (pin "1") (pinfunction "1_1") (pintype "passive"))
    )
    (net (code "50") (name "Net-(JK2-Pad3)") (class "Default")
      (node (ref "JK2") (pin "3") (pinfunction "3_3") (pintype "passive"))
      (node (ref "JP2") (pin "2") (pinfunction "2_2") (pintype "passive"))
    )
    (net (code "51") (name "Net-(JK2-Pad4)") (class "Default")
      (node (ref "JK2") (pin "4") (pinfunction "4_4") (pintype "passive"))
      (node (ref "JP2") (pin "3") (pinfunction "3_3") (pintype "passive"))
    )
    (net (code "52") (name "Net-(JK2-Pad5)") (class "Default")
      (node (ref "JK2") (pin "5") (pinfunction "5_5") (pintype "passive"))
      (node (ref "JP2") (pin "1") (pinfunction "1_1") (pintype "passive"))
    )
    (net (code "53") (name "Net-(JK3-Pad3)") (class "Default")
      (node (ref "JK3") (pin "3") (pinfunction "3_3") (pintype "passive"))
      (node (ref "JP3") (pin "2") (pinfunction "2_2") (pintype "passive"))
    )
    (net (code "54") (name "Net-(JK3-Pad4)") (class "Default")
      (node (ref "JK3") (pin "4") (pinfunction "4_4") (pintype "passive"))
      (node (ref "JP3") (pin "3") (pinfunction "3_3") (pintype "passive"))
    )
    (net (code "55") (name "Net-(JK3-Pad5)") (class "Default")
      (node (ref "JK3") (pin "5") (pinfunction "5_5") (pintype "passive"))
      (node (ref "JP3") (pin "1") (pinfunction "1_1") (pintype "passive"))
    )
    (net (code "56") (name "Net-(JK4-Pad3)") (class "Default")
      (node (ref "JK4") (pin "3") (pinfunction "3_3") (pintype "passive"))
      (node (ref "JP4") (pin "2") (pinfunction "2_2") (pintype "passive"))
    )
    (net (code "57") (name "Net-(JK4-Pad4)") (class "Default")
      (node (ref "JK4") (pin "4") (pinfunction "4_4") (pintype "passive"))
      (node (ref "JP4") (pin "3") (pinfunction "3_3") (pintype "passive"))
    )
    (net (code "58") (name "Net-(JK4-Pad5)") (class "Default")
      (node (ref "JK4") (pin "5") (pinfunction "5_5") (pintype "passive"))
      (node (ref "JP4") (pin "1") (pinfunction "1_1") (pintype "passive"))
    )
    (net (code "59") (name "Net-(LED0-C)") (class "Default")
      (node (ref "LED0") (pin "2") (pinfunction "C_2") (pintype "passive"))
      (node (ref "R7") (pin "2") (pinfunction "2_2") (pintype "passive"))
    )
    (net (code "60") (name "Net-(LED1-C)") (class "Default")
      (node (ref "LED1") (pin "2") (pinfunction "C_2") (pintype "passive"))
      (node (ref "R4-1") (pin "1") (pinfunction "1_1") (pintype "passive"))
    )
    (net (code "61") (name "Net-(LED2-C)") (class "Default")
      (node (ref "LED2") (pin "2") (pinfunction "C_2") (pintype "passive"))
      (node (ref "R4-2") (pin "1") (pinfunction "1_1") (pintype "passive"))
    )
    (net (code "62") (name "Net-(LED3-C)") (class "Default")
      (node (ref "LED3") (pin "2") (pinfunction "C_2") (pintype "passive"))
      (node (ref "R4-3") (pin "1") (pinfunction "1_1") (pintype "passive"))
    )
    (net (code "63") (name "Net-(LED4-C)") (class "Default")
      (node (ref "LED4") (pin "2") (pinfunction "C_2") (pintype "passive"))
      (node (ref "R4-4") (pin "1") (pinfunction "1_1") (pintype "passive"))
    )
    (net (code "64") (name "Net-(P2-D+)") (class "Default")
      (node (ref "P2") (pin "3") (pinfunction "D+_3") (pintype "passive"))
      (node (ref "U4") (pin "5") (pinfunction "D+_5") (pintype "passive"))
    )
    (net (code "65") (name "Net-(P2-D-)") (class "Default")
      (node (ref "P2") (pin "2") (pinfunction "D-_2") (pintype "passive"))
      (node (ref "U4") (pin "6") (pinfunction "D-_6") (pintype "passive"))
    )
    (net (code "66") (name "Net-(P3-Pad2)") (class "Default")
      (node (ref "P3") (pin "2") (pinfunction "2_2") (pintype "passive"))
      (node (ref "R1") (pin "1") (pintype "passive"))
    )
    (net (code "67") (name "Net-(Q1-B)") (class "Default")
      (node (ref "Q1") (pin "1") (pinfunction "B_1") (pintype "passive"))
      (node (ref "R2-1") (pin "1") (pinfunction "1_1") (pintype "passive"))
      (node (ref "R3-1") (pin "2") (pintype "passive"))
    )
    (net (code "68") (name "Net-(Q2-B)") (class "Default")
      (node (ref "Q2") (pin "1") (pinfunction "B_1") (pintype "passive"))
      (node (ref "R2-2") (pin "1") (pinfunction "1_1") (pintype "passive"))
      (node (ref "R3-2") (pin "2") (pintype "passive"))
    )
    (net (code "69") (name "Net-(Q3-B)") (class "Default")
      (node (ref "Q3") (pin "1") (pinfunction "B_1") (pintype "passive"))
      (node (ref "R2-3") (pin "1") (pinfunction "1_1") (pintype "passive"))
      (node (ref "R3-3") (pin "2") (pintype "passive"))
    )
    (net (code "70") (name "Net-(Q4-B)") (class "Default")
      (node (ref "Q4") (pin "1") (pinfunction "B_1") (pintype "passive"))
      (node (ref "R2-4") (pin "1") (pinfunction "1_1") (pintype "passive"))
      (node (ref "R3-4") (pin "2") (pintype "passive"))
    )
    (net (code "71") (name "Net-(U4-V3)") (class "Default")
      (node (ref "C7") (pin "2") (pintype "passive"))
      (node (ref "U4") (pin "4") (pinfunction "V3_4") (pintype "passive"))
    )
    (net (code "72") (name "Net-(U5-EN)") (class "Default")
      (node (ref "C9") (pin "1") (pinfunction "1_1") (pintype "passive"))
      (node (ref "R6") (pin "1") (pinfunction "1_1") (pintype "passive"))
      (node (ref "U5") (pin "3") (pinfunction "EN_3") (pintype "passive"))
    )
    (net (code "73") (name "Net-(U5-GPIO13)") (class "Default")
      (node (ref "R7") (pin "1") (pinfunction "1_1") (pintype "passive"))
      (node (ref "U5") (pin "7") (pinfunction "GPIO13_7") (pintype "passive"))
    )
    (net (code "74") (name "Net-(U5-RST)") (class "Default")
      (node (ref "R9") (pin "1") (pinfunction "1_1") (pintype "passive"))
      (node (ref "U5") (pin "24") (pinfunction "RST_24") (pintype "passive"))
    )
    (net (code "75") (name "VBUS") (class "Default")
      (node (ref "C8") (pin "2") (pinfunction "2_2") (pintype "passive"))
      (node (ref "P2") (pin "1") (pinfunction "VCC_1") (pintype "passive"))
      (node (ref "U4") (pin "16") (pinfunction "VCC_16") (pintype "passive"))
    )
    (net (code "76") (name "unconnected-(U4-CTS#-Pad9)") (class "Default")
      (node (ref "U4") (pin "9") (pinfunction "CTS#_9") (pintype "passive"))
    )
    (net (code "77") (name "unconnected-(U4-DCD#-Pad12)") (class "Default")
      (node (ref "U4") (pin "12") (pinfunction "DCD#_12") (pintype "passive"))
    )
    (net (code "78") (name "unconnected-(U4-DSR#-Pad10)") (class "Default")
      (node (ref "U4") (pin "10") (pinfunction "DSR#_10") (pintype "passive"))
    )
    (net (code "79") (name "unconnected-(U4-DTR#-Pad13)") (class "Default")
      (node (ref "U4") (pin "13") (pinfunction "DTR#_13") (pintype "passive"))
    )
    (net (code "80") (name "unconnected-(U4-R232-Pad15)") (class "Default")
      (node (ref "U4") (pin "15") (pinfunction "R232_15") (pintype "passive"))
    )
    (net (code "81") (name "unconnected-(U4-RI#-Pad11)") (class "Default")
      (node (ref "U4") (pin "11") (pinfunction "RI#_11") (pintype "passive"))
    )
    (net (code "82") (name "unconnected-(U4-RTS#-Pad14)") (class "Default")
      (node (ref "U4") (pin "14") (pinfunction "RTS#_14") (pintype "passive"))
    )
    (net (code "83") (name "unconnected-(U4-XI-Pad7)") (class "Default")
      (node (ref "U4") (pin "7") (pinfunction "XI_7") (pintype "passive"))
    )
    (net (code "84") (name "unconnected-(U4-XO-Pad8)") (class "Default")
      (node (ref "U4") (pin "8") (pinfunction "XO_8") (pintype "passive"))
    )
    (net (code "85") (name "unconnected-(U5-ADC-Pad2)") (class "Default")
      (node (ref "U5") (pin "2") (pinfunction "ADC_2") (pintype "passive"))
    )
    (net (code "86") (name "unconnected-(U5-ANT-Pad1)") (class "Default")
      (node (ref "U5") (pin "1") (pinfunction "ANT_1") (pintype "passive"))
    )
    (net (code "87") (name "unconnected-(U5-GPIO2-Pad9)") (class "Default")
      (node (ref "U5") (pin "9") (pinfunction "GPIO2_9") (pintype "passive"))
    )
    (net (code "88") (name "unconnected-(U5-GPIO6-Pad16)") (class "Default")
      (node (ref "U5") (pin "16") (pinfunction "GPIO6_16") (pintype "passive"))
    )
    (net (code "89") (name "unconnected-(U5-GPIO7-Pad17)") (class "Default")
      (node (ref "U5") (pin "17") (pinfunction "GPIO7_17") (pintype "passive"))
    )
    (net (code "90") (name "unconnected-(U5-GPIO8-Pad18)") (class "Default")
      (node (ref "U5") (pin "18") (pinfunction "GPIO8_18") (pintype "passive"))
    )
    (net (code "91") (name "unconnected-(U5-GPIO11-Pad15)") (class "Default")
      (node (ref "U5") (pin "15") (pinfunction "GPIO11_15") (pintype "passive"))
    )
    (net (code "92") (name "unconnected-(U5-GPIO16-Pad4)") (class "Default")
      (node (ref "U5") (pin "4") (pinfunction "GPIO16_4") (pintype "passive"))
    )
    (net (code "93") (name "unconnected-(U5-RX-Pad21)") (class "Default")
      (node (ref "U5") (pin "21") (pinfunction "RX_21") (pintype "passive"))
    )
    (net (code "94") (name "unconnected-(U5-TX-Pad22)") (class "Default")
      (node (ref "U5") (pin "22") (pinfunction "TX_22") (pintype "passive"))
    )
    (net (code "95") (name "unconnected-(U6A-PA0-WKUP-Pad10)") (class "Default")
      (node (ref "U6") (pin "10") (pinfunction "PA0-WKUP_10") (pintype "bidirectional+no_connect"))
    )
    (net (code "96") (name "unconnected-(U6A-PA1-Pad11)") (class "Default")
      (node (ref "U6") (pin "11") (pinfunction "PA1_11") (pintype "bidirectional+no_connect"))
    )
    (net (code "97") (name "unconnected-(U6A-PA8-Pad29)") (class "Default")
      (node (ref "U6") (pin "29") (pinfunction "PA8_29") (pintype "bidirectional"))
    )
    (net (code "98") (name "unconnected-(U6A-PA11-Pad32)") (class "Default")
      (node (ref "U6") (pin "32") (pinfunction "PA11_32") (pintype "bidirectional+no_connect"))
    )
    (net (code "99") (name "unconnected-(U6A-PA12-Pad33)") (class "Default")
      (node (ref "U6") (pin "33") (pinfunction "PA12_33") (pintype "bidirectional+no_connect"))
    )
    (net (code "100") (name "unconnected-(U6A-PA13-Pad34)") (class "Default")
      (node (ref "U6") (pin "34") (pinfunction "PA13_34") (pintype "bidirectional+no_connect"))
    )
    (net (code "101") (name "unconnected-(U6A-PB5-Pad41)") (class "Default")
      (node (ref "U6") (pin "41") (pinfunction "PB5_41") (pintype "bidirectional+no_connect"))
    )
    (net (code "102") (name "unconnected-(U6A-PB6-Pad42)") (class "Default")
      (node (ref "U6") (pin "42") (pinfunction "PB6_42") (pintype "bidirectional+no_connect"))
    )
    (net (code "103") (name "unconnected-(U6A-PB7-Pad43)") (class "Default")
      (node (ref "U6") (pin "43") (pinfunction "PB7_43") (pintype "bidirectional+no_connect"))
    )
    (net (code "104") (name "unconnected-(U6A-PB12-Pad25)") (class "Default")
      (node (ref "U6") (pin "25") (pinfunction "PB12_25") (pintype "bidirectional+no_connect"))
    )
    (net (code "105") (name "unconnected-(U6A-PB13-Pad26)") (class "Default")
      (node (ref "U6") (pin "26") (pinfunction "PB13_26") (pintype "bidirectional+no_connect"))
    )
    (net (code "106") (name "unconnected-(U6A-PB14-Pad27)") (class "Default")
      (node (ref "U6") (pin "27") (pinfunction "PB14_27") (pintype "bidirectional+no_connect"))
    )
    (net (code "107") (name "unconnected-(U6A-PB15-Pad28)") (class "Default")
      (node (ref "U6") (pin "28") (pinfunction "PB15_28") (pintype "bidirectional+no_connect"))
    )
    (net (code "108") (name "unconnected-(U6A-PC13-TAMPER-RTC-Pad2)") (class "Default")
      (node (ref "U6") (pin "2") (pinfunction "PC13-TAMPER-RTC_2") (pintype "bidirectional+no_connect"))
    )
    (net (code "109") (name "unconnected-(U6A-PC14-OSC32_IN-Pad3)") (class "Default")
      (node (ref "U6") (pin "3") (pinfunction "PC14-OSC32_IN_3") (pintype "bidirectional+no_connect"))
    )
    (net (code "110") (name "unconnected-(U6A-PC15-OSC32_OUT-Pad4)") (class "Default")
      (node (ref "U6") (pin "4") (pinfunction "PC15-OSC32_OUT_4") (pintype "bidirectional+no_connect"))
    )
  )
)
